# Dendro.net
KiCad netlist of a schematic drawn in EAGLE
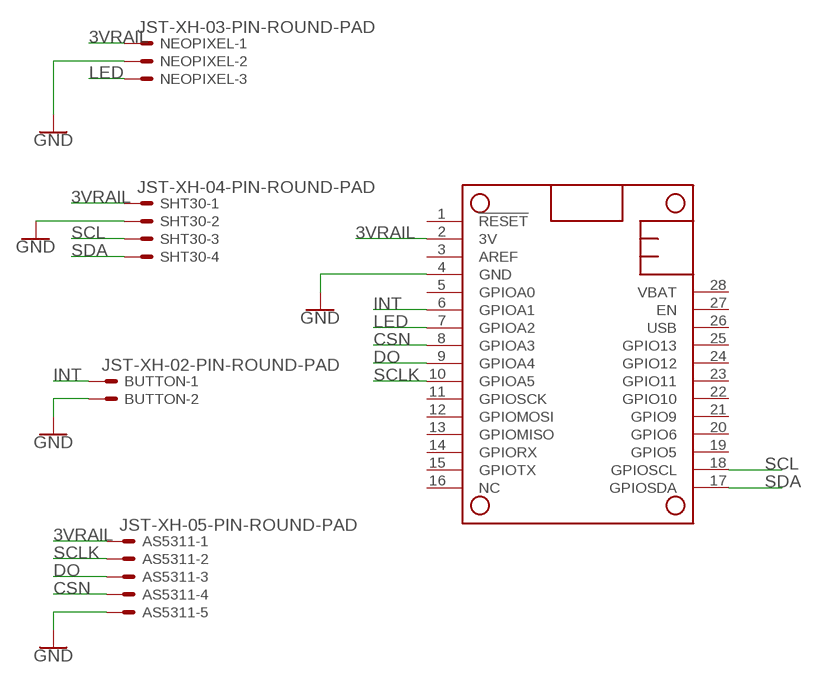
[diagram p0: schematic, sheet 1]

(export (version "E")
  (design (tool "Eeschema 10.0.6"))
  (components
    (comp (ref "AS5311")
      (value "JST-XH-05-PIN-ROUND-PAD")
      (footprint "eagle-import:JST-XH-05-PACKAGE-ROUND-PAD")
      (libsource (lib "eagle-import") (part "JST-XH-05-PIN-ROUND-PAD"))
    )
    (comp (ref "BUTTON")
      (value "JST-XH-02-PIN-ROUND-PAD")
      (footprint "eagle-import:JST-XH-02-PACKAGE-ROUND-PAD")
      (libsource (lib "eagle-import") (part "JST-XH-02-PIN-ROUND-PAD"))
    )
    (comp (ref "MS1")
      (value "FEATHERWING")
      (footprint "eagle-import:FEATHERWING")
      (libsource (lib "eagle-import") (part "FEATHERWING"))
    )
    (comp (ref "NEOPIXEL")
      (value "JST-XH-03-PIN-ROUND-PAD")
      (footprint "eagle-import:JST-XH-03-PACKAGE-ROUND-PAD")
      (libsource (lib "eagle-import") (part "JST-XH-03-PIN-ROUND-PAD"))
    )
    (comp (ref "SHT30")
      (value "JST-XH-04-PIN-ROUND-PAD")
      (footprint "eagle-import:JST-XH-04-PACKAGE-ROUND-PAD")
      (libsource (lib "eagle-import") (part "JST-XH-04-PIN-ROUND-PAD"))
    )
  )
  (nets
    (net (code "1") (name "/3VRAIL") (class "Default")
      (node (ref "AS5311") (pin "1") (pinfunction "S_1") (pintype "passive"))
      (node (ref "MS1") (pin "2") (pinfunction "3V_2") (pintype "power_in"))
      (node (ref "NEOPIXEL") (pin "1") (pinfunction "S_1") (pintype "passive"))
      (node (ref "SHT30") (pin "1") (pinfunction "S_1") (pintype "passive"))
    )
    (net (code "2") (name "/CSN") (class "Default")
      (node (ref "AS5311") (pin "4") (pinfunction "S_4") (pintype "passive"))
      (node (ref "MS1") (pin "8") (pinfunction "GPIOA3_8") (pintype "bidirectional"))
    )
    (net (code "3") (name "/DO") (class "Default")
      (node (ref "AS5311") (pin "3") (pinfunction "S_3") (pintype "passive"))
      (node (ref "MS1") (pin "9") (pinfunction "GPIOA4_9") (pintype "bidirectional"))
    )
    (net (code "4") (name "/INT") (class "Default")
      (node (ref "BUTTON") (pin "1") (pinfunction "S_1") (pintype "passive"))
      (node (ref "MS1") (pin "6") (pinfunction "GPIOA1_6") (pintype "bidirectional"))
    )
    (net (code "5") (name "/LED") (class "Default")
      (node (ref "MS1") (pin "7") (pinfunction "GPIOA2_7") (pintype "bidirectional"))
      (node (ref "NEOPIXEL") (pin "3") (pinfunction "S_3") (pintype "passive"))
    )
    (net (code "6") (name "/SCL") (class "Default")
      (node (ref "MS1") (pin "18") (pinfunction "GPIOSCL_18") (pintype "bidirectional"))
      (node (ref "SHT30") (pin "3") (pinfunction "S_3") (pintype "passive"))
    )
    (net (code "7") (name "/SCLK") (class "Default")
      (node (ref "AS5311") (pin "2") (pinfunction "S_2") (pintype "passive"))
      (node (ref "MS1") (pin "10") (pinfunction "GPIOA5_10") (pintype "bidirectional"))
    )
    (net (code "8") (name "/SDA") (class "Default")
      (node (ref "MS1") (pin "17") (pinfunction "GPIOSDA_17") (pintype "bidirectional"))
      (node (ref "SHT30") (pin "4") (pinfunction "S_4") (pintype "passive"))
    )
    (net (code "9") (name "/USB") (class "Default")
      (node (ref "MS1") (pin "26") (pinfunction "USB_26") (pintype "power_in"))
    )
    (net (code "10") (name "/VBAT") (class "Default")
      (node (ref "MS1") (pin "28") (pinfunction "VBAT_28") (pintype "power_in"))
    )
    (net (code "11") (name "GND") (class "Default")
      (node (ref "AS5311") (pin "5") (pinfunction "S_5") (pintype "passive"))
      (node (ref "BUTTON") (pin "2") (pinfunction "S_2") (pintype "passive"))
      (node (ref "MS1") (pin "4") (pinfunction "GND_4") (pintype "power_in"))
      (node (ref "NEOPIXEL") (pin "2") (pinfunction "S_2") (pintype "passive"))
      (node (ref "SHT30") (pin "2") (pinfunction "S_2") (pintype "passive"))
    )
    (net (code "12") (name "unconnected-(MS1-AREF-Pad3)") (class "Default")
      (node (ref "MS1") (pin "3") (pinfunction "AREF_3") (pintype "passive"))
    )
    (net (code "13") (name "unconnected-(MS1-EN-Pad27)") (class "Default")
      (node (ref "MS1") (pin "27") (pinfunction "EN_27") (pintype "passive"))
    )
    (net (code "14") (name "unconnected-(MS1-GPIO5-Pad19)") (class "Default")
      (node (ref "MS1") (pin "19") (pinfunction "GPIO5_19") (pintype "bidirectional"))
    )
    (net (code "15") (name "unconnected-(MS1-GPIO6-Pad20)") (class "Default")
      (node (ref "MS1") (pin "20") (pinfunction "GPIO6_20") (pintype "bidirectional"))
    )
    (net (code "16") (name "unconnected-(MS1-GPIO9-Pad21)") (class "Default")
      (node (ref "MS1") (pin "21") (pinfunction "GPIO9_21") (pintype "bidirectional"))
    )
    (net (code "17") (name "unconnected-(MS1-GPIO10-Pad22)") (class "Default")
      (node (ref "MS1") (pin "22") (pinfunction "GPIO10_22") (pintype "bidirectional"))
    )
    (net (code "18") (name "unconnected-(MS1-GPIO11-Pad23)") (class "Default")
      (node (ref "MS1") (pin "23") (pinfunction "GPIO11_23") (pintype "bidirectional"))
    )
    (net (code "19") (name "unconnected-(MS1-GPIO12-Pad24)") (class "Default")
      (node (ref "MS1") (pin "24") (pinfunction "GPIO12_24") (pintype "bidirectional"))
    )
    (net (code "20") (name "unconnected-(MS1-GPIO13-Pad25)") (class "Default")
      (node (ref "MS1") (pin "25") (pinfunction "GPIO13_25") (pintype "bidirectional"))
    )
    (net (code "21") (name "unconnected-(MS1-GPIOA0-Pad5)") (class "Default")
      (node (ref "MS1") (pin "5") (pinfunction "GPIOA0_5") (pintype "bidirectional"))
    )
    (net (code "22") (name "unconnected-(MS1-GPIOMISO-Pad13)") (class "Default")
      (node (ref "MS1") (pin "13") (pinfunction "GPIOMISO_13") (pintype "bidirectional"))
    )
    (net (code "23") (name "unconnected-(MS1-GPIOMOSI-Pad12)") (class "Default")
      (node (ref "MS1") (pin "12") (pinfunction "GPIOMOSI_12") (pintype "bidirectional"))
    )
    (net (code "24") (name "unconnected-(MS1-GPIORX-Pad14)") (class "Default")
      (node (ref "MS1") (pin "14") (pinfunction "GPIORX_14") (pintype "bidirectional"))
    )
    (net (code "25") (name "unconnected-(MS1-GPIOSCK-Pad11)") (class "Default")
      (node (ref "MS1") (pin "11") (pinfunction "GPIOSCK_11") (pintype "bidirectional"))
    )
    (net (code "26") (name "unconnected-(MS1-GPIOTX-Pad15)") (class "Default")
      (node (ref "MS1") (pin "15") (pinfunction "GPIOTX_15") (pintype "bidirectional"))
    )
    (net (code "27") (name "unconnected-(MS1-NC-Pad16)") (class "Default")
      (node (ref "MS1") (pin "16") (pinfunction "NC_16") (pintype "passive"))
    )
    (net (code "28") (name "unconnected-(MS1-~{RESET}-Pad1)") (class "Default")
      (node (ref "MS1") (pin "1") (pinfunction "~{RESET}_1") (pintype "input"))
    )
  )
)
